# VLNA_1_1.net
KiCad netlist of a schematic drawn in EAGLE
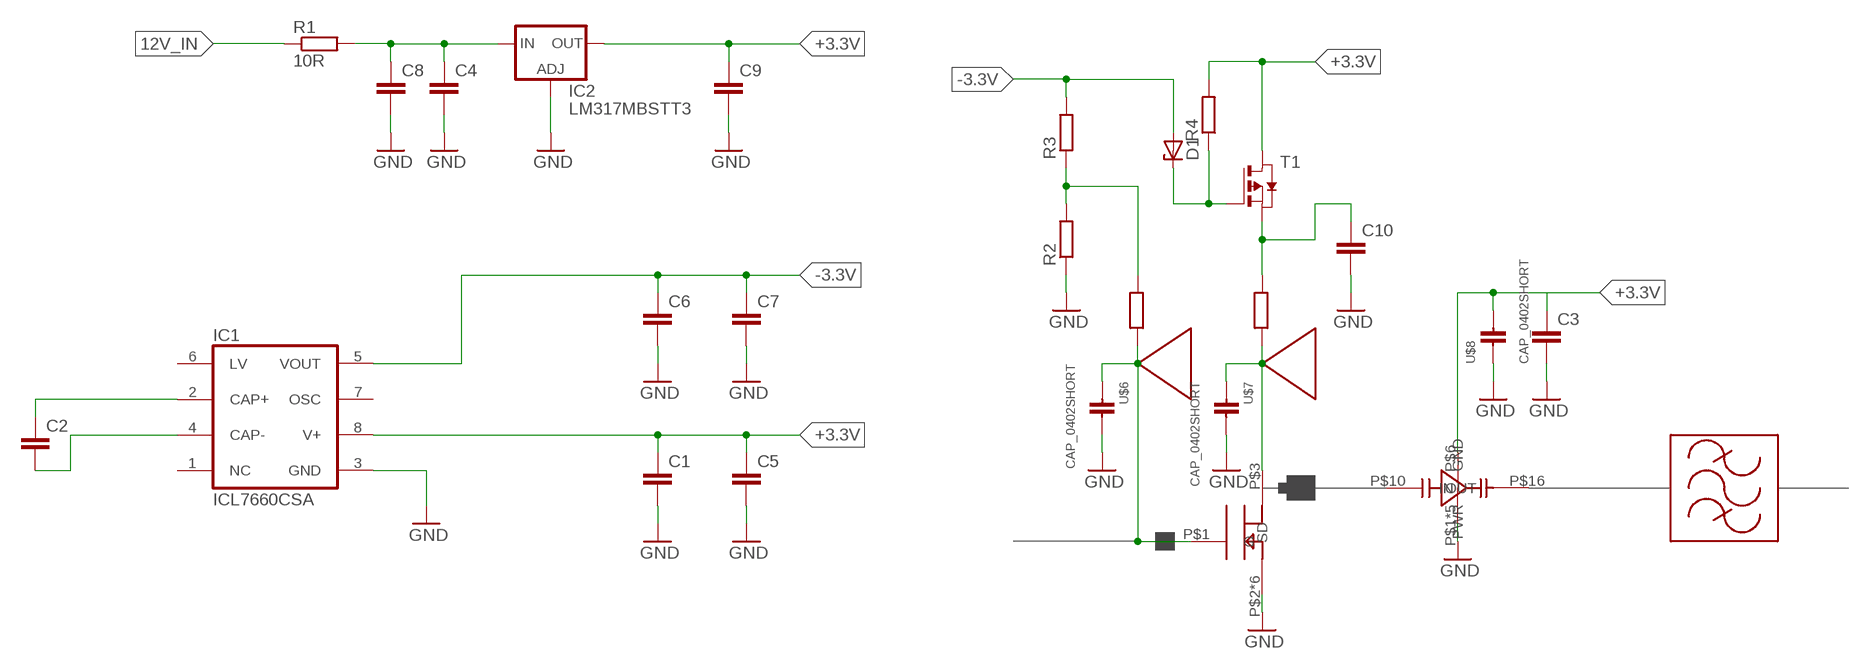
[diagram p0: schematic, sheet 1]

(export (version "E")
  (design (tool "Eeschema 10.0.6"))
  (components
    (comp (ref "C1")
      (value "C-EUC0603")
      (footprint "eagle-import:C0603")
      (libsource (lib "eagle-import") (part "C-EUC0603"))
    )
    (comp (ref "C2")
      (value "C-EUC0603")
      (footprint "eagle-import:C0603")
      (libsource (lib "eagle-import") (part "C-EUC0603"))
    )
    (comp (ref "C3")
      (value "C-EUC0402")
      (footprint "eagle-import:C0402")
      (libsource (lib "eagle-import") (part "C-EUC0402"))
    )
    (comp (ref "C4")
      (value "C-EUC0603")
      (footprint "eagle-import:C0603")
      (libsource (lib "eagle-import") (part "C-EUC0603"))
    )
    (comp (ref "C5")
      (value "C-EUC0603")
      (footprint "eagle-import:C0603")
      (libsource (lib "eagle-import") (part "C-EUC0603"))
    )
    (comp (ref "C6")
      (value "C-EUC0603")
      (footprint "eagle-import:C0603")
      (libsource (lib "eagle-import") (part "C-EUC0603"))
    )
    (comp (ref "C7")
      (value "C-EUC0603")
      (footprint "eagle-import:C0603")
      (libsource (lib "eagle-import") (part "C-EUC0603"))
    )
    (comp (ref "C8")
      (value "C-EUC0805")
      (footprint "eagle-import:C0805")
      (libsource (lib "eagle-import") (part "C-EUC0805"))
    )
    (comp (ref "C9")
      (value "C-EUC0603")
      (footprint "eagle-import:C0603")
      (libsource (lib "eagle-import") (part "C-EUC0603"))
    )
    (comp (ref "C10")
      (value "C-EUC0603")
      (footprint "eagle-import:C0603")
      (libsource (lib "eagle-import") (part "C-EUC0603"))
    )
    (comp (ref "D1")
      (value "ZENER-DIODESOD80C")
      (footprint "eagle-import:SOD80C")
      (libsource (lib "eagle-import") (part "ZENER-DIODESOD80C"))
    )
    (comp (ref "IC1")
      (value "ICL7660CSA")
      (footprint "eagle-import:SO08")
      (fields (field (name "MF") "MAXIM"))
      (libsource (lib "eagle-import") (part "ICL7660CSA"))
    )
    (comp (ref "IC2")
      (value "LM317MBSTT3")
      (footprint "eagle-import:SOT223")
      (libsource (lib "eagle-import") (part "LM317?MBSTT3"))
    )
    (comp (ref "R1")
      (value "10R")
      (footprint "eagle-import:R0805")
      (libsource (lib "eagle-import") (part "R-EU_R0805"))
    )
    (comp (ref "R2")
      (value "R-EU_R0603")
      (footprint "eagle-import:R0603")
      (libsource (lib "eagle-import") (part "R-EU_R0603"))
    )
    (comp (ref "R3")
      (value "R-EU_R0603")
      (footprint "eagle-import:R0603")
      (libsource (lib "eagle-import") (part "R-EU_R0603"))
    )
    (comp (ref "R4")
      (value "R-EU_R0603")
      (footprint "eagle-import:R0603")
      (libsource (lib "eagle-import") (part "R-EU_R0603"))
    )
    (comp (ref "T1")
      (value "PMOSSOT23")
      (footprint "eagle-import:SOT-23")
      (libsource (lib "eagle-import") (part "PMOSSOT23"))
    )
    (comp (ref "U$2")
      (value "24GHZ_OP")
      (footprint "eagle-import:FILTER")
      (libsource (lib "eagle-import") (part "24GHZ_OP"))
    )
    (comp (ref "U$3")
      (value "CE3520K3")
      (footprint "eagle-import:MICROX")
      (libsource (lib "eagle-import") (part "CE3520K3"))
    )
    (comp (ref "U$4")
      (value "HMC341")
      (footprint "eagle-import:HMC")
      (libsource (lib "eagle-import") (part "HMC341"))
    )
    (comp (ref "U$5")
      (value "RES_0402SHORT")
      (footprint "eagle-import:0402S")
      (libsource (lib "eagle-import") (part "RES_0402SHORT"))
    )
    (comp (ref "U$6")
      (value "CAP_0402SHORT")
      (footprint "eagle-import:0402S")
      (libsource (lib "eagle-import") (part "CAP_0402SHORT"))
    )
    (comp (ref "U$7")
      (value "CAP_0402SHORT")
      (footprint "eagle-import:0402S")
      (libsource (lib "eagle-import") (part "CAP_0402SHORT"))
    )
    (comp (ref "U$8")
      (value "CAP_0402SHORT")
      (footprint "eagle-import:0402S")
      (libsource (lib "eagle-import") (part "CAP_0402SHORT"))
    )
    (comp (ref "U$9")
      (value "RES_0402SHORT")
      (footprint "eagle-import:0402S")
      (libsource (lib "eagle-import") (part "RES_0402SHORT"))
    )
    (comp (ref "U$10")
      (value "STUB")
      (footprint "eagle-import:QTR_STUB")
      (libsource (lib "eagle-import") (part "STUB"))
    )
    (comp (ref "U$11")
      (value "STUB")
      (footprint "eagle-import:QTR_STUB")
      (libsource (lib "eagle-import") (part "STUB"))
    )
  )
  (nets
    (net (code "1") (name "+3.3V") (class "Default")
      (node (ref "C1") (pin "1") (pinfunction "1_1") (pintype "passive"))
      (node (ref "C3") (pin "1") (pinfunction "1_1") (pintype "passive"))
      (node (ref "C5") (pin "1") (pinfunction "1_1") (pintype "passive"))
      (node (ref "C9") (pin "1") (pinfunction "1_1") (pintype "passive"))
      (node (ref "IC1") (pin "8") (pinfunction "V+_8") (pintype "power_in"))
      (node (ref "IC2") (pin "4") (pinfunction "OUT_4") (pintype "passive"))
      (node (ref "R4") (pin "2") (pinfunction "2_2") (pintype "passive"))
      (node (ref "T1") (pin "1") (pinfunction "D_1") (pintype "passive"))
      (node (ref "U$4") (pin "P$6") (pinfunction "PWR_P$6") (pintype "power_in"))
      (node (ref "U$8") (pin "P$2") (pinfunction "P$2_P$2") (pintype "bidirectional"))
    )
    (net (code "2") (name "-3.3V") (class "Default")
      (node (ref "C6") (pin "1") (pinfunction "1_1") (pintype "passive"))
      (node (ref "C7") (pin "1") (pinfunction "1_1") (pintype "passive"))
      (node (ref "D1") (pin "A") (pinfunction "A_A") (pintype "passive"))
      (node (ref "IC1") (pin "5") (pinfunction "VOUT_5") (pintype "output"))
      (node (ref "R3") (pin "2") (pinfunction "2_2") (pintype "passive"))
    )
    (net (code "3") (name "12V_IN") (class "Default")
      (node (ref "R1") (pin "1") (pinfunction "1_1") (pintype "passive"))
    )
    (net (code "4") (name "GND") (class "Default")
      (node (ref "C1") (pin "2") (pinfunction "2_2") (pintype "passive"))
      (node (ref "C10") (pin "2") (pinfunction "2_2") (pintype "passive"))
      (node (ref "C3") (pin "2") (pinfunction "2_2") (pintype "passive"))
      (node (ref "C4") (pin "2") (pinfunction "2_2") (pintype "passive"))
      (node (ref "C5") (pin "2") (pinfunction "2_2") (pintype "passive"))
      (node (ref "C6") (pin "2") (pinfunction "2_2") (pintype "passive"))
      (node (ref "C7") (pin "2") (pinfunction "2_2") (pintype "passive"))
      (node (ref "C8") (pin "2") (pinfunction "2_2") (pintype "passive"))
      (node (ref "C9") (pin "2") (pinfunction "2_2") (pintype "passive"))
      (node (ref "IC1") (pin "3") (pinfunction "GND_3") (pintype "power_in"))
      (node (ref "IC2") (pin "1") (pinfunction "ADJ_1") (pintype "input"))
      (node (ref "R2") (pin "1") (pinfunction "1_1") (pintype "passive"))
      (node (ref "U$3") (pin "P$2") (pinfunction "S_P$2") (pintype "bidirectional"))
      (node (ref "U$3") (pin "P$4") (pinfunction "S_P$4") (pintype "bidirectional"))
      (node (ref "U$3") (pin "P$5") (pinfunction "S_P$5") (pintype "bidirectional"))
      (node (ref "U$3") (pin "P$6") (pinfunction "S_P$6") (pintype "bidirectional"))
      (node (ref "U$3") (pin "P$7") (pinfunction "S_P$7") (pintype "bidirectional"))
      (node (ref "U$3") (pin "P$8") (pinfunction "S_P$8") (pintype "bidirectional"))
      (node (ref "U$4") (pin "P$1") (pinfunction "GND_P$1") (pintype "bidirectional"))
      (node (ref "U$4") (pin "P$11") (pinfunction "GND_P$11") (pintype "bidirectional"))
      (node (ref "U$4") (pin "P$15") (pinfunction "GND_P$15") (pintype "bidirectional"))
      (node (ref "U$4") (pin "P$17") (pinfunction "GND_P$17") (pintype "bidirectional"))
      (node (ref "U$4") (pin "P$9") (pinfunction "GND_P$9") (pintype "bidirectional"))
      (node (ref "U$6") (pin "P$2") (pinfunction "P$2_P$2") (pintype "bidirectional"))
      (node (ref "U$7") (pin "P$2") (pinfunction "P$2_P$2") (pintype "bidirectional"))
      (node (ref "U$8") (pin "P$1") (pinfunction "P$1_P$1") (pintype "bidirectional"))
    )
    (net (code "5") (name "Net-(IC1-CAP+)") (class "Default")
      (node (ref "C2") (pin "1") (pinfunction "1_1") (pintype "passive"))
      (node (ref "IC1") (pin "2") (pinfunction "CAP+_2") (pintype "passive"))
    )
    (net (code "6") (name "Net-(IC1-CAP-)") (class "Default")
      (node (ref "C2") (pin "2") (pinfunction "2_2") (pintype "passive"))
      (node (ref "IC1") (pin "4") (pinfunction "CAP-_4") (pintype "passive"))
    )
    (net (code "7") (name "Net-(IC2-IN)") (class "Default")
      (node (ref "C4") (pin "1") (pinfunction "1_1") (pintype "passive"))
      (node (ref "C8") (pin "1") (pinfunction "1_1") (pintype "passive"))
      (node (ref "IC2") (pin "3") (pinfunction "IN_3") (pintype "input"))
      (node (ref "R1") (pin "2") (pinfunction "2_2") (pintype "passive"))
    )
    (net (code "8") (name "Net-(R2-Pad2)") (class "Default")
      (node (ref "R2") (pin "2") (pinfunction "2_2") (pintype "passive"))
      (node (ref "R3") (pin "1") (pinfunction "1_1") (pintype "passive"))
      (node (ref "U$5") (pin "P$2") (pinfunction "P$2_P$2") (pintype "bidirectional"))
    )
    (net (code "9") (name "Net-(T1-G)") (class "Default")
      (node (ref "D1") (pin "C") (pinfunction "C_C") (pintype "passive"))
      (node (ref "R4") (pin "1") (pinfunction "1_1") (pintype "passive"))
      (node (ref "T1") (pin "3") (pinfunction "G_3") (pintype "passive"))
    )
    (net (code "10") (name "Net-(T1-S)") (class "Default")
      (node (ref "C10") (pin "1") (pinfunction "1_1") (pintype "passive"))
      (node (ref "T1") (pin "2") (pinfunction "S_2") (pintype "passive"))
      (node (ref "U$9") (pin "P$2") (pinfunction "P$2_P$2") (pintype "bidirectional"))
    )
    (net (code "11") (name "Net-(U$3-D)") (class "Default")
      (node (ref "U$3") (pin "P$3") (pinfunction "D_P$3") (pintype "bidirectional"))
      (node (ref "U$7") (pin "P$1") (pinfunction "P$1_P$1") (pintype "bidirectional"))
      (node (ref "U$9") (pin "P$1") (pinfunction "P$1_P$1") (pintype "bidirectional"))
    )
    (net (code "12") (name "Net-(U$3-G)") (class "Default")
      (node (ref "U$3") (pin "P$1") (pinfunction "G_P$1") (pintype "bidirectional"))
      (node (ref "U$5") (pin "P$1") (pinfunction "P$1_P$1") (pintype "bidirectional"))
      (node (ref "U$6") (pin "P$1") (pinfunction "P$1_P$1") (pintype "bidirectional"))
    )
    (net (code "13") (name "unconnected-(IC1-LV-Pad6)") (class "Default")
      (node (ref "IC1") (pin "6") (pinfunction "LV_6") (pintype "passive"))
    )
    (net (code "14") (name "unconnected-(IC1-NC-Pad1)") (class "Default")
      (node (ref "IC1") (pin "1") (pinfunction "NC_1") (pintype "no_connect"))
    )
    (net (code "15") (name "unconnected-(IC1-OSC-Pad7)") (class "Default")
      (node (ref "IC1") (pin "7") (pinfunction "OSC_7") (pintype "output"))
    )
    (net (code "16") (name "unconnected-(U$4-IN-PadP$10)") (class "Default")
      (node (ref "U$4") (pin "P$10") (pinfunction "IN_P$10") (pintype "bidirectional"))
    )
    (net (code "17") (name "unconnected-(U$4-OUT-PadP$16)") (class "Default")
      (node (ref "U$4") (pin "P$16") (pinfunction "OUT_P$16") (pintype "bidirectional"))
    )
  )
)
